# Cycle-Controller-Onboard.net
KiCad netlist of a schematic drawn in Altium Designer
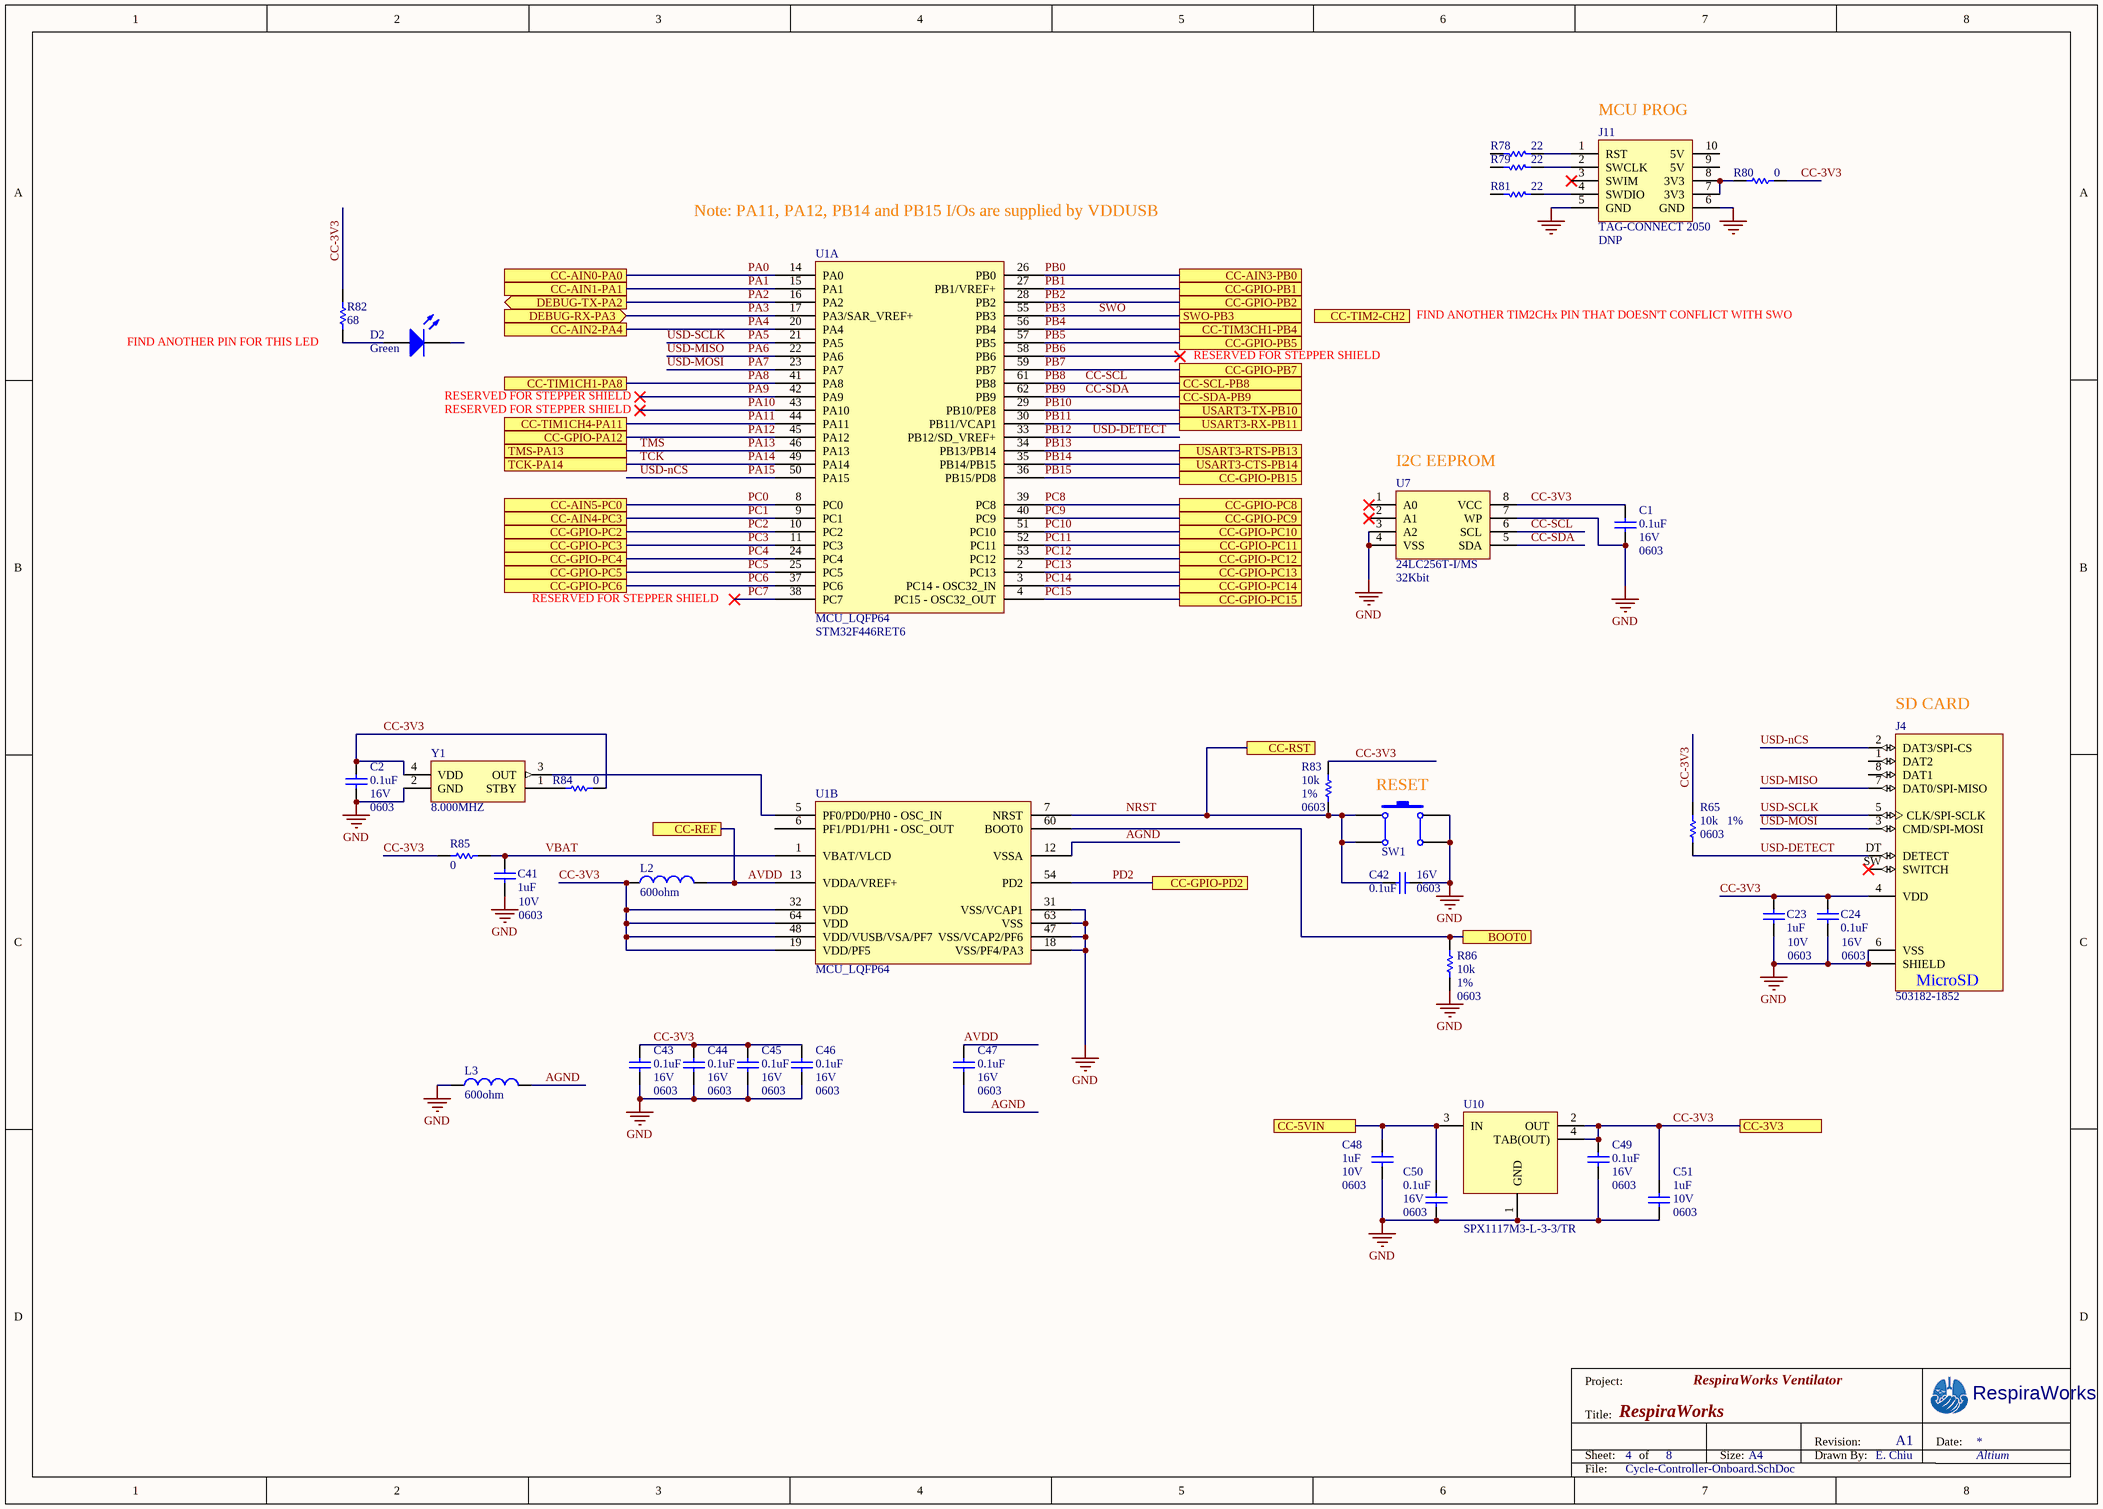
[diagram p0: Cycle-Controller-Onboard.SchDoc]

(export (version "E")
  (design (tool "Eeschema 10.0.6"))
  (components
    (comp (ref "C1")
      (value "0.1uF")
      (footprint "CAP0603")
      (description "Cap 0603")
      (fields
        (field (name "MANUFACTURER") "Yageo")
        (field (name "VOLTAGE") "16V")
        (field (name "PCB PACKAGE") "0603")
        (field (name "Comment") "CAP 0603")
      )
      (libsource (lib "generic") (part "CAP 0603"))
    )
    (comp (ref "C2")
      (value "0.1uF")
      (footprint "CAP0603")
      (description "Cap 0603")
      (fields
        (field (name "MANUFACTURER") "Yageo")
        (field (name "VOLTAGE") "16V")
        (field (name "PCB PACKAGE") "0603")
        (field (name "Comment") "CAP 0603")
      )
      (libsource (lib "generic") (part "CAP 0603"))
    )
    (comp (ref "C23")
      (value "1uF")
      (footprint "CAP0603")
      (description "Cap 0603")
      (fields
        (field (name "MANUFACTURER") "Yageo")
        (field (name "VOLTAGE") "10V")
        (field (name "PCB PACKAGE") "0603")
        (field (name "Comment") "CAP 0603")
      )
      (libsource (lib "generic") (part "CAP 0603"))
    )
    (comp (ref "C24")
      (value "0.1uF")
      (footprint "CAP0603")
      (description "Cap 0603")
      (fields
        (field (name "MANUFACTURER") "Yageo")
        (field (name "VOLTAGE") "16V")
        (field (name "PCB PACKAGE") "0603")
        (field (name "Comment") "CAP 0603")
      )
      (libsource (lib "generic") (part "CAP 0603"))
    )
    (comp (ref "C41")
      (value "1uF")
      (footprint "CAP0603")
      (description "Cap 0603")
      (fields
        (field (name "MANUFACTURER") "Yageo")
        (field (name "VOLTAGE") "10V")
        (field (name "PCB PACKAGE") "0603")
        (field (name "Comment") "CAP 0603")
      )
      (libsource (lib "generic") (part "CAP 0603"))
    )
    (comp (ref "C42")
      (value "0.1uF")
      (footprint "CAP0603")
      (description "Cap 0603")
      (fields
        (field (name "MANUFACTURER") "Yageo")
        (field (name "VOLTAGE") "16V")
        (field (name "PCB PACKAGE") "0603")
        (field (name "Comment") "CAP 0603")
      )
      (libsource (lib "generic") (part "CAP 0603"))
    )
    (comp (ref "C43")
      (value "0.1uF")
      (footprint "CAP0603")
      (description "Cap 0603")
      (fields
        (field (name "MANUFACTURER") "Yageo")
        (field (name "VOLTAGE") "16V")
        (field (name "PCB PACKAGE") "0603")
        (field (name "Comment") "CAP 0603")
      )
      (libsource (lib "generic") (part "CAP 0603"))
    )
    (comp (ref "C44")
      (value "0.1uF")
      (footprint "CAP0603")
      (description "Cap 0603")
      (fields
        (field (name "MANUFACTURER") "Yageo")
        (field (name "VOLTAGE") "16V")
        (field (name "PCB PACKAGE") "0603")
        (field (name "Comment") "CAP 0603")
      )
      (libsource (lib "generic") (part "CAP 0603"))
    )
    (comp (ref "C45")
      (value "0.1uF")
      (footprint "CAP0603")
      (description "Cap 0603")
      (fields
        (field (name "MANUFACTURER") "Yageo")
        (field (name "VOLTAGE") "16V")
        (field (name "PCB PACKAGE") "0603")
        (field (name "Comment") "CAP 0603")
      )
      (libsource (lib "generic") (part "CAP 0603"))
    )
    (comp (ref "C46")
      (value "0.1uF")
      (footprint "CAP0603")
      (description "Cap 0603")
      (fields
        (field (name "MANUFACTURER") "Yageo")
        (field (name "VOLTAGE") "16V")
        (field (name "PCB PACKAGE") "0603")
        (field (name "Comment") "CAP 0603")
      )
      (libsource (lib "generic") (part "CAP 0603"))
    )
    (comp (ref "C47")
      (value "0.1uF")
      (footprint "CAP0603")
      (description "Cap 0603")
      (fields
        (field (name "MANUFACTURER") "Yageo")
        (field (name "VOLTAGE") "16V")
        (field (name "PCB PACKAGE") "0603")
        (field (name "Comment") "CAP 0603")
      )
      (libsource (lib "generic") (part "CAP 0603"))
    )
    (comp (ref "C48")
      (value "1uF")
      (footprint "CAP0603")
      (description "Cap 0603")
      (fields
        (field (name "MANUFACTURER") "Yageo")
        (field (name "VOLTAGE") "10V")
        (field (name "PCB PACKAGE") "0603")
        (field (name "Comment") "CAP 0603")
      )
      (libsource (lib "generic") (part "CAP 0603"))
    )
    (comp (ref "C49")
      (value "0.1uF")
      (footprint "CAP0603")
      (description "Cap 0603")
      (fields
        (field (name "MANUFACTURER") "Yageo")
        (field (name "VOLTAGE") "16V")
        (field (name "PCB PACKAGE") "0603")
        (field (name "Comment") "CAP 0603")
      )
      (libsource (lib "generic") (part "CAP 0603"))
    )
    (comp (ref "C50")
      (value "0.1uF")
      (footprint "CAP0603")
      (description "Cap 0603")
      (fields
        (field (name "MANUFACTURER") "Yageo")
        (field (name "VOLTAGE") "16V")
        (field (name "PCB PACKAGE") "0603")
        (field (name "Comment") "CAP 0603")
      )
      (libsource (lib "generic") (part "CAP 0603"))
    )
    (comp (ref "C51")
      (value "1uF")
      (footprint "CAP0603")
      (description "Cap 0603")
      (fields
        (field (name "MANUFACTURER") "Yageo")
        (field (name "VOLTAGE") "10V")
        (field (name "PCB PACKAGE") "0603")
        (field (name "Comment") "CAP 0603")
      )
      (libsource (lib "generic") (part "CAP 0603"))
    )
    (comp (ref "D2")
      (value "Green")
      (footprint "LED0603")
      (description "LED 0603")
      (fields (field (name "MANUFACTURER") "Lite-On"))
      (libsource (lib "generic") (part "LED 0603"))
    )
    (comp (ref "J4")
      (value "503182-1852")
      (footprint "molex:503182-1852")
      (description "10 _8 + 2_ Position Card Connector microSD Surface Mount, Right Angle Gold")
      (fields (field (name "MANUFACTURER") "Molex") (field (name "DIGI-KEY_PART_NUMBER") "WM12834CT-ND"))
      (libsource (lib "molex") (part "503182-1852"))
    )
    (comp (ref "J11")
      (value "TAG-CONNECT 2050")
      (footprint "TAG-CONNECT-2050")
      (description "10-pin TAG-CONNECT Bed of Nails footprint")
      (fields (field (name "DO NOT POPULATE") "DNP"))
      (libsource (lib "special") (part "TC-2050-STLINK"))
    )
    (comp (ref "L2")
      (value "600ohm")
      (footprint "IND0603")
      (description "Ferrite 0603")
      (fields (field (name "MANUFACTURER") "Wurth") (field (name "Comment") "BEAD"))
      (libsource (lib "generic") (part "FERRITE 0603"))
    )
    (comp (ref "L3")
      (value "600ohm")
      (footprint "IND0603")
      (description "Ferrite 0603")
      (fields (field (name "MANUFACTURER") "Wurth") (field (name "Comment") "BEAD"))
      (libsource (lib "generic") (part "FERRITE 0603"))
    )
    (comp (ref "R65")
      (value "10k")
      (footprint "RES0603")
      (description "Res 0603")
      (fields
        (field (name "MANUFACTURER") "Panasonic")
        (field (name "PCB PACKAGE") "0603")
        (field (name "TOLERANCE") "1%")
        (field (name "Comment") "RES 0603")
      )
      (libsource (lib "generic") (part "RES 0603"))
    )
    (comp (ref "R78")
      (value "22")
      (footprint "RES0603")
      (description "Res 0603")
      (fields (field (name "MANUFACTURER") "Yageo") (field (name "TOLERANCE") "1%"))
      (libsource (lib "generic") (part "RES 0603"))
    )
    (comp (ref "R79")
      (value "22")
      (footprint "RES0603")
      (description "Res 0603")
      (fields (field (name "MANUFACTURER") "Yageo") (field (name "TOLERANCE") "1%"))
      (libsource (lib "generic") (part "RES 0603"))
    )
    (comp (ref "R80")
      (value "0")
      (footprint "RES0603")
      (description "Res 0603")
      (fields (field (name "MANUFACTURER") "Panasonic") (field (name "Comment") "RES 0603"))
      (libsource (lib "generic") (part "RES 0603"))
    )
    (comp (ref "R81")
      (value "22")
      (footprint "RES0603")
      (description "Res 0603")
      (fields (field (name "MANUFACTURER") "Yageo") (field (name "TOLERANCE") "1%"))
      (libsource (lib "generic") (part "RES 0603"))
    )
    (comp (ref "R82")
      (value "68")
      (footprint "RES0603")
      (description "Res 0603")
      (fields (field (name "MANUFACTURER") "Panasonic") (field (name "TOLERANCE") "1%"))
      (libsource (lib "generic") (part "RES 0603"))
    )
    (comp (ref "R83")
      (value "10k")
      (footprint "RES0603")
      (description "Res 0603")
      (fields
        (field (name "MANUFACTURER") "Panasonic")
        (field (name "PCB PACKAGE") "0603")
        (field (name "TOLERANCE") "1%")
        (field (name "Comment") "RES 0603")
      )
      (libsource (lib "generic") (part "RES 0603"))
    )
    (comp (ref "R84")
      (value "0")
      (footprint "RES0603")
      (description "Res 0603")
      (fields (field (name "MANUFACTURER") "Panasonic") (field (name "Comment") "RES 0603"))
      (libsource (lib "generic") (part "RES 0603"))
    )
    (comp (ref "R85")
      (value "0")
      (footprint "RES0603")
      (description "Res 0603")
      (fields (field (name "MANUFACTURER") "Panasonic") (field (name "Comment") "RES 0603"))
      (libsource (lib "generic") (part "RES 0603"))
    )
    (comp (ref "R86")
      (value "10k")
      (footprint "RES0603")
      (description "Res 0603")
      (fields
        (field (name "MANUFACTURER") "Panasonic")
        (field (name "PCB PACKAGE") "0603")
        (field (name "TOLERANCE") "1%")
        (field (name "Comment") "RES 0603")
      )
      (libsource (lib "generic") (part "RES 0603"))
    )
    (comp (ref "SW1")
      (value "BUTTON")
      (footprint "PB-6MM-J-LEAD")
      (description "PUSHBUTTON, 6MM SQ, TACT, J-Lead")
      (fields (field (name "MANUFACTURER") "E-Switch"))
      (libsource (lib "e-switch") (part "PUSHBUTTON-SQ-6MM-TACT-J-LEAD"))
    )
    (comp (ref "U1")
      (value "MCU_LQFP64")
      (footprint "64-LQFP")
      (description "IC MCU 32BIT 512KB FLASH 64LQFP")
      (fields (field (name "MANUFACTURER P/N") "STM32F446RET6") (field (name "MANUFACTURER") "ST Micro"))
      (libsource (lib "Nucleo_64") (part "MCU_LQFP64"))
    )
    (comp (ref "U7")
      (value "32Kbit")
      (footprint "8-MSOP")
      (description "IC EEPROM 256KBIT I2C 400KHZ 8MSOP")
      (fields
        (field (name "MANUFACTURER") "Microchip")
        (field (name "TOLERANCE") "25ppm")
        (field (name "MANUFACTURER P/N") "24LC256T-I/MS")
      )
      (libsource (lib "microchip") (part "24LC256T-I/MS"))
    )
    (comp (ref "U10")
      (value "NCP1117ST33T3G")
      (footprint "3-SOT223")
      (description "LDO, 3.3V out, 1A, 20V in, SOT-223, 0.8W Pd max")
      (fields (field (name "MANUFACTURER") "Exar") (field (name "MANUFACTURER P/N") "SPX1117M3-L-3-3/TR"))
      (libsource (lib "on-semi") (part "NCP1117ST33T3G"))
    )
    (comp (ref "Y1")
      (value "8.000MHZ")
      (footprint "4-OSC3225")
      (description "OSC MEMS 8.000MHZ CMOS SMD")
      (fields (field (name "MANUFACTURER") "Abracon") (field (name "TOLERANCE") "50ppm"))
      (libsource (lib "abracon") (part "ASEMB-8.000MHZ-LC-T"))
    )
  )
  (nets
    (net (code "1") (name "/AGND") (class "Default")
      (node (ref "C47") (pin "2") (pinfunction "2_2") (pintype "passive"))
      (node (ref "L3") (pin "2") (pinfunction "2_2") (pintype "passive"))
      (node (ref "U1") (pin "12") (pinfunction "VSSA_12") (pintype "passive"))
    )
    (net (code "2") (name "/AVDD") (class "Default")
      (node (ref "C47") (pin "1") (pinfunction "1_1") (pintype "passive"))
      (node (ref "L2") (pin "2") (pinfunction "2_2") (pintype "passive"))
      (node (ref "U1") (pin "13") (pinfunction "VDDA/VREF+_13") (pintype "passive"))
    )
    (net (code "3") (name "/BOOT0") (class "Default")
      (node (ref "R86") (pin "2") (pinfunction "2_2") (pintype "passive"))
      (node (ref "U1") (pin "60") (pinfunction "BOOT0_60") (pintype "passive"))
    )
    (net (code "4") (name "/CC-3V3") (class "Default")
      (node (ref "C1") (pin "1") (pinfunction "1_1") (pintype "passive"))
      (node (ref "C2") (pin "1") (pinfunction "1_1") (pintype "passive"))
      (node (ref "C23") (pin "1") (pinfunction "1_1") (pintype "passive"))
      (node (ref "C24") (pin "1") (pinfunction "1_1") (pintype "passive"))
      (node (ref "C43") (pin "1") (pinfunction "1_1") (pintype "passive"))
      (node (ref "C44") (pin "1") (pinfunction "1_1") (pintype "passive"))
      (node (ref "C45") (pin "1") (pinfunction "1_1") (pintype "passive"))
      (node (ref "C46") (pin "1") (pinfunction "1_1") (pintype "passive"))
      (node (ref "C49") (pin "1") (pinfunction "1_1") (pintype "passive"))
      (node (ref "C51") (pin "1") (pinfunction "1_1") (pintype "passive"))
      (node (ref "J4") (pin "4") (pinfunction "VDD_4") (pintype "power_in"))
      (node (ref "L2") (pin "1") (pinfunction "1_1") (pintype "passive"))
      (node (ref "R65") (pin "2") (pinfunction "2_2") (pintype "passive"))
      (node (ref "R80") (pin "2") (pinfunction "2_2") (pintype "passive"))
      (node (ref "R82") (pin "2") (pinfunction "2_2") (pintype "passive"))
      (node (ref "R83") (pin "2") (pinfunction "2_2") (pintype "passive"))
      (node (ref "R84") (pin "1") (pinfunction "1_1") (pintype "passive"))
      (node (ref "R85") (pin "2") (pinfunction "2_2") (pintype "passive"))
      (node (ref "U1") (pin "19") (pinfunction "VDD/PF5_19") (pintype "passive"))
      (node (ref "U1") (pin "32") (pinfunction "VDD_32") (pintype "passive"))
      (node (ref "U1") (pin "48") (pinfunction "VDD/VUSB/VSA/PF7_48") (pintype "passive"))
      (node (ref "U1") (pin "64") (pinfunction "VDD_64") (pintype "passive"))
      (node (ref "U10") (pin "2") (pinfunction "OUT_2") (pintype "passive"))
      (node (ref "U10") (pin "4") (pinfunction "TAB(OUT)_4") (pintype "passive"))
      (node (ref "U7") (pin "8") (pinfunction "VCC_8") (pintype "passive"))
      (node (ref "Y1") (pin "4") (pinfunction "VDD_4") (pintype "passive"))
    )
    (net (code "5") (name "/CC-5VIN") (class "Default")
      (node (ref "C48") (pin "1") (pinfunction "1_1") (pintype "passive"))
      (node (ref "C50") (pin "1") (pinfunction "1_1") (pintype "passive"))
      (node (ref "U10") (pin "3") (pinfunction "IN_3") (pintype "passive"))
    )
    (net (code "6") (name "/CC-SCL") (class "Default")
      (node (ref "U1") (pin "61") (pinfunction "PB8_61") (pintype "passive"))
      (node (ref "U7") (pin "6") (pinfunction "SCL_6") (pintype "passive"))
    )
    (net (code "7") (name "/CC-SDA") (class "Default")
      (node (ref "U1") (pin "62") (pinfunction "PB9_62") (pintype "passive"))
      (node (ref "U7") (pin "5") (pinfunction "SDA_5") (pintype "passive"))
    )
    (net (code "9") (name "/NRST") (class "Default")
      (node (ref "C42") (pin "1") (pinfunction "1_1") (pintype "passive"))
      (node (ref "R83") (pin "1") (pinfunction "1_1") (pintype "passive"))
      (node (ref "SW1") (pin "1") (pinfunction "1_1") (pintype "passive"))
      (node (ref "SW1") (pin "2") (pinfunction "2_2") (pintype "passive"))
      (node (ref "U1") (pin "7") (pinfunction "NRST_7") (pintype "passive"))
    )
    (net (code "10") (name "/PA0") (class "Default")
      (node (ref "U1") (pin "14") (pinfunction "PA0_14") (pintype "passive"))
    )
    (net (code "11") (name "/PA1") (class "Default")
      (node (ref "U1") (pin "15") (pinfunction "PA1_15") (pintype "passive"))
    )
    (net (code "12") (name "/PA2") (class "Default")
      (node (ref "U1") (pin "16") (pinfunction "PA2_16") (pintype "passive"))
    )
    (net (code "13") (name "/PA3") (class "Default")
      (node (ref "U1") (pin "17") (pinfunction "PA3/SAR_VREF+_17") (pintype "passive"))
    )
    (net (code "14") (name "/PA4") (class "Default")
      (node (ref "U1") (pin "20") (pinfunction "PA4_20") (pintype "passive"))
    )
    (net (code "15") (name "/PA5") (class "Default")
      (node (ref "J4") (pin "5") (pinfunction "CLK/SPI-SCLK_5") (pintype "bidirectional"))
      (node (ref "U1") (pin "21") (pinfunction "PA5_21") (pintype "passive"))
    )
    (net (code "16") (name "/PA6") (class "Default")
      (node (ref "J4") (pin "7") (pinfunction "DAT0/SPI-MISO_7") (pintype "bidirectional"))
      (node (ref "U1") (pin "22") (pinfunction "PA6_22") (pintype "passive"))
    )
    (net (code "17") (name "/PA7") (class "Default")
      (node (ref "J4") (pin "3") (pinfunction "CMD/SPI-MOSI_3") (pintype "bidirectional"))
      (node (ref "U1") (pin "23") (pinfunction "PA7_23") (pintype "passive"))
    )
    (net (code "18") (name "/PA8") (class "Default")
      (node (ref "U1") (pin "41") (pinfunction "PA8_41") (pintype "passive"))
    )
    (net (code "19") (name "/PA9") (class "Default")
      (node (ref "U1") (pin "42") (pinfunction "PA9_42") (pintype "passive+no_connect"))
    )
    (net (code "20") (name "/PA10") (class "Default")
      (node (ref "U1") (pin "43") (pinfunction "PA10_43") (pintype "passive+no_connect"))
    )
    (net (code "21") (name "/PA11") (class "Default")
      (node (ref "U1") (pin "44") (pinfunction "PA11_44") (pintype "passive"))
    )
    (net (code "22") (name "/PA12") (class "Default")
      (node (ref "U1") (pin "45") (pinfunction "PA12_45") (pintype "passive"))
    )
    (net (code "23") (name "/PA13") (class "Default")
      (node (ref "U1") (pin "46") (pinfunction "PA13_46") (pintype "passive"))
    )
    (net (code "24") (name "/PA14") (class "Default")
      (node (ref "U1") (pin "49") (pinfunction "PA14_49") (pintype "passive"))
    )
    (net (code "25") (name "/PA15") (class "Default")
      (node (ref "J4") (pin "2") (pinfunction "DAT3/SPI-CS_2") (pintype "bidirectional"))
      (node (ref "U1") (pin "50") (pinfunction "PA15_50") (pintype "passive"))
    )
    (net (code "26") (name "/PB0") (class "Default")
      (node (ref "U1") (pin "26") (pinfunction "PB0_26") (pintype "passive"))
    )
    (net (code "27") (name "/PB1") (class "Default")
      (node (ref "U1") (pin "27") (pinfunction "PB1/VREF+_27") (pintype "passive"))
    )
    (net (code "28") (name "/PB2") (class "Default")
      (node (ref "U1") (pin "28") (pinfunction "PB2_28") (pintype "passive"))
    )
    (net (code "29") (name "/PB3") (class "Default")
      (node (ref "U1") (pin "55") (pinfunction "PB3_55") (pintype "passive"))
    )
    (net (code "30") (name "/PB4") (class "Default")
      (node (ref "U1") (pin "56") (pinfunction "PB4_56") (pintype "passive"))
    )
    (net (code "31") (name "/PB5") (class "Default")
      (node (ref "U1") (pin "57") (pinfunction "PB5_57") (pintype "passive"))
    )
    (net (code "32") (name "/PB6") (class "Default")
      (node (ref "U1") (pin "58") (pinfunction "PB6_58") (pintype "passive+no_connect"))
    )
    (net (code "33") (name "/PB7") (class "Default")
      (node (ref "U1") (pin "59") (pinfunction "PB7_59") (pintype "passive"))
    )
    (net (code "34") (name "/PB10") (class "Default")
      (node (ref "U1") (pin "29") (pinfunction "PB10/PE8_29") (pintype "passive"))
    )
    (net (code "35") (name "/PB11") (class "Default")
      (node (ref "U1") (pin "30") (pinfunction "PB11/VCAP1_30") (pintype "passive"))
    )
    (net (code "36") (name "/PB12") (class "Default")
      (node (ref "J4") (pin "DT") (pinfunction "DETECT_DT") (pintype "bidirectional"))
      (node (ref "R65") (pin "1") (pinfunction "1_1") (pintype "passive"))
      (node (ref "U1") (pin "33") (pinfunction "PB12/SD_VREF+_33") (pintype "passive"))
    )
    (net (code "37") (name "/PB13") (class "Default")
      (node (ref "U1") (pin "34") (pinfunction "PB13/PB14_34") (pintype "passive"))
    )
    (net (code "38") (name "/PB14") (class "Default")
      (node (ref "U1") (pin "35") (pinfunction "PB14/PB15_35") (pintype "passive"))
    )
    (net (code "39") (name "/PB15") (class "Default")
      (node (ref "U1") (pin "36") (pinfunction "PB15/PD8_36") (pintype "passive"))
    )
    (net (code "40") (name "/PC0") (class "Default")
      (node (ref "U1") (pin "8") (pinfunction "PC0_8") (pintype "passive"))
    )
    (net (code "41") (name "/PC1") (class "Default")
      (node (ref "U1") (pin "9") (pinfunction "PC1_9") (pintype "passive"))
    )
    (net (code "42") (name "/PC2") (class "Default")
      (node (ref "U1") (pin "10") (pinfunction "PC2_10") (pintype "passive"))
    )
    (net (code "43") (name "/PC3") (class "Default")
      (node (ref "U1") (pin "11") (pinfunction "PC3_11") (pintype "passive"))
    )
    (net (code "44") (name "/PC4") (class "Default")
      (node (ref "U1") (pin "24") (pinfunction "PC4_24") (pintype "passive"))
    )
    (net (code "45") (name "/PC5") (class "Default")
      (node (ref "U1") (pin "25") (pinfunction "PC5_25") (pintype "passive"))
    )
    (net (code "46") (name "/PC6") (class "Default")
      (node (ref "U1") (pin "37") (pinfunction "PC6_37") (pintype "passive"))
    )
    (net (code "47") (name "/PC7") (class "Default")
      (node (ref "U1") (pin "38") (pinfunction "PC7_38") (pintype "passive+no_connect"))
    )
    (net (code "48") (name "/PC8") (class "Default")
      (node (ref "U1") (pin "39") (pinfunction "PC8_39") (pintype "passive"))
    )
    (net (code "49") (name "/PC9") (class "Default")
      (node (ref "U1") (pin "40") (pinfunction "PC9_40") (pintype "passive"))
    )
    (net (code "50") (name "/PC10") (class "Default")
      (node (ref "U1") (pin "51") (pinfunction "PC10_51") (pintype "passive"))
    )
    (net (code "51") (name "/PC11") (class "Default")
      (node (ref "U1") (pin "52") (pinfunction "PC11_52") (pintype "passive"))
    )
    (net (code "52") (name "/PC12") (class "Default")
      (node (ref "U1") (pin "53") (pinfunction "PC12_53") (pintype "passive"))
    )
    (net (code "53") (name "/PC13") (class "Default")
      (node (ref "U1") (pin "2") (pinfunction "PC13_2") (pintype "passive"))
    )
    (net (code "54") (name "/PC14") (class "Default")
      (node (ref "U1") (pin "3") (pinfunction "PC14_-_OSC32_IN_3") (pintype "passive"))
    )
    (net (code "55") (name "/PC15") (class "Default")
      (node (ref "U1") (pin "4") (pinfunction "PC15_-_OSC32_OUT_4") (pintype "passive"))
    )
    (net (code "56") (name "/PD2") (class "Default")
      (node (ref "U1") (pin "54") (pinfunction "PD2_54") (pintype "passive"))
    )
    (net (code "57") (name "/VBAT") (class "Default")
      (node (ref "C41") (pin "1") (pinfunction "1_1") (pintype "passive"))
      (node (ref "R85") (pin "1") (pinfunction "1_1") (pintype "passive"))
      (node (ref "U1") (pin "1") (pinfunction "VBAT/VLCD_1") (pintype "passive"))
    )
    (net (code "58") (name "GND") (class "Default")
      (node (ref "C1") (pin "2") (pinfunction "2_2") (pintype "passive"))
      (node (ref "C2") (pin "2") (pinfunction "2_2") (pintype "passive"))
      (node (ref "C23") (pin "2") (pinfunction "2_2") (pintype "passive"))
      (node (ref "C24") (pin "2") (pinfunction "2_2") (pintype "passive"))
      (node (ref "C41") (pin "2") (pinfunction "2_2") (pintype "passive"))
      (node (ref "C42") (pin "2") (pinfunction "2_2") (pintype "passive"))
      (node (ref "C43") (pin "2") (pinfunction "2_2") (pintype "passive"))
      (node (ref "C44") (pin "2") (pinfunction "2_2") (pintype "passive"))
      (node (ref "C45") (pin "2") (pinfunction "2_2") (pintype "passive"))
      (node (ref "C46") (pin "2") (pinfunction "2_2") (pintype "passive"))
      (node (ref "C48") (pin "2") (pinfunction "2_2") (pintype "passive"))
      (node (ref "C49") (pin "2") (pinfunction "2_2") (pintype "passive"))
      (node (ref "C50") (pin "2") (pinfunction "2_2") (pintype "passive"))
      (node (ref "C51") (pin "2") (pinfunction "2_2") (pintype "passive"))
      (node (ref "J11") (pin "5") (pinfunction "GND_5") (pintype "passive"))
      (node (ref "J11") (pin "6") (pinfunction "GND_6") (pintype "passive"))
      (node (ref "J4") (pin "6") (pinfunction "VSS_6") (pintype "power_in"))
      (node (ref "J4") (pin "P1") (pinfunction "SHIELD_P1") (pintype "passive"))
      (node (ref "J4") (pin "P2") (pinfunction "SHIELD_P2") (pintype "passive"))
      (node (ref "J4") (pin "P3") (pinfunction "SHIELD_P3") (pintype "passive"))
      (node (ref "J4") (pin "P4") (pinfunction "SHIELD_P4") (pintype "passive"))
      (node (ref "J4") (pin "P5") (pinfunction "SHIELD_P5") (pintype "passive"))
      (node (ref "L3") (pin "1") (pinfunction "1_1") (pintype "passive"))
      (node (ref "R86") (pin "1") (pinfunction "1_1") (pintype "passive"))
      (node (ref "SW1") (pin "3") (pinfunction "3_3") (pintype "passive"))
      (node (ref "SW1") (pin "4") (pinfunction "4_4") (pintype "passive"))
      (node (ref "U1") (pin "18") (pinfunction "VSS/PF4/PA3_18") (pintype "passive"))
      (node (ref "U1") (pin "31") (pinfunction "VSS/VCAP1_31") (pintype "passive"))
      (node (ref "U1") (pin "47") (pinfunction "VSS/VCAP2/PF6_47") (pintype "passive"))
      (node (ref "U1") (pin "63") (pinfunction "VSS_63") (pintype "passive"))
      (node (ref "U10") (pin "1") (pinfunction "GND_1") (pintype "passive"))
      (node (ref "U7") (pin "3") (pinfunction "A2_3") (pintype "passive"))
      (node (ref "U7") (pin "4") (pinfunction "VSS_4") (pintype "passive"))
      (node (ref "U7") (pin "7") (pinfunction "WP_7") (pintype "passive"))
      (node (ref "Y1") (pin "2") (pinfunction "GND_2") (pintype "passive"))
    )
    (net (code "59") (name "Net-(D2-PadA)") (class "Default")
      (node (ref "D2") (pin "A") (pinfunction "A_A") (pintype "passive"))
      (node (ref "R82") (pin "1") (pinfunction "1_1") (pintype "passive"))
    )
    (net (code "60") (name "Net-(J11-3V3-Pad7)") (class "Default")
      (node (ref "J11") (pin "7") (pinfunction "3V3_7") (pintype "passive"))
      (node (ref "J11") (pin "8") (pinfunction "3V3_8") (pintype "passive"))
      (node (ref "R80") (pin "1") (pinfunction "1_1") (pintype "passive"))
    )
    (net (code "61") (name "Net-(J11-RST)") (class "Default")
      (node (ref "J11") (pin "1") (pinfunction "RST_1") (pintype "passive"))
      (node (ref "R78") (pin "1") (pinfunction "1_1") (pintype "passive"))
    )
    (net (code "62") (name "Net-(J11-SWCLK)") (class "Default")
      (node (ref "J11") (pin "2") (pinfunction "SWCLK_2") (pintype "passive"))
      (node (ref "R79") (pin "1") (pinfunction "1_1") (pintype "passive"))
    )
    (net (code "63") (name "Net-(J11-SWDIO)") (class "Default")
      (node (ref "J11") (pin "4") (pinfunction "SWDIO_4") (pintype "passive"))
      (node (ref "R81") (pin "1") (pinfunction "1_1") (pintype "passive"))
    )
    (net (code "64") (name "Net-(U1B-PF0{slash}PD0{slash}PH0_-_OSC_IN)") (class "Default")
      (node (ref "U1") (pin "5") (pinfunction "PF0/PD0/PH0_-_OSC_IN_5") (pintype "passive"))
      (node (ref "Y1") (pin "3") (pinfunction "OUT_3") (pintype "output"))
    )
    (net (code "65") (name "Net-(Y1-STBY)") (class "Default")
      (node (ref "R84") (pin "2") (pinfunction "2_2") (pintype "passive"))
      (node (ref "Y1") (pin "1") (pinfunction "STBY_1") (pintype "passive"))
    )
    (net (code "66") (name "unconnected-(D2-PadK)") (class "Default")
      (node (ref "D2") (pin "K") (pinfunction "K_K") (pintype "passive"))
    )
    (net (code "67") (name "unconnected-(J4-DAT1-Pad8)") (class "Default")
      (node (ref "J4") (pin "8") (pinfunction "DAT1_8") (pintype "bidirectional"))
    )
    (net (code "68") (name "unconnected-(J4-DAT2-Pad1)") (class "Default")
      (node (ref "J4") (pin "1") (pinfunction "DAT2_1") (pintype "bidirectional"))
    )
    (net (code "69") (name "unconnected-(J4-SWITCH-PadSW)") (class "Default")
      (node (ref "J4") (pin "SW") (pinfunction "SWITCH_SW") (pintype "bidirectional+no_connect"))
    )
    (net (code "70") (name "unconnected-(J11-5V-Pad9)") (class "Default")
      (node (ref "J11") (pin "9") (pinfunction "5V_9") (pintype "passive"))
    )
    (net (code "71") (name "unconnected-(J11-5V-Pad10)") (class "Default")
      (node (ref "J11") (pin "10") (pinfunction "5V_10") (pintype "passive"))
    )
    (net (code "72") (name "unconnected-(J11-SWIM-Pad3)") (class "Default")
      (node (ref "J11") (pin "3") (pinfunction "SWIM_3") (pintype "passive+no_connect"))
    )
    (net (code "73") (name "unconnected-(R78-Pad2)") (class "Default")
      (node (ref "R78") (pin "2") (pinfunction "2_2") (pintype "passive"))
    )
    (net (code "74") (name "unconnected-(R79-Pad2)") (class "Default")
      (node (ref "R79") (pin "2") (pinfunction "2_2") (pintype "passive"))
    )
    (net (code "75") (name "unconnected-(R81-Pad2)") (class "Default")
      (node (ref "R81") (pin "2") (pinfunction "2_2") (pintype "passive"))
    )
    (net (code "76") (name "unconnected-(U1B-PF1{slash}PD1{slash}PH1_-_OSC_OUT-Pad6)") (class "Default")
      (node (ref "U1") (pin "6") (pinfunction "PF1/PD1/PH1_-_OSC_OUT_6") (pintype "passive"))
    )
    (net (code "77") (name "unconnected-(U7-A0-Pad1)") (class "Default")
      (node (ref "U7") (pin "1") (pinfunction "A0_1") (pintype "passive+no_connect"))
    )
    (net (code "78") (name "unconnected-(U7-A1-Pad2)") (class "Default")
      (node (ref "U7") (pin "2") (pinfunction "A1_2") (pintype "passive+no_connect"))
    )
  )
)
